# GPS_lte2.net
KiCad netlist of a schematic drawn in Altium Designer
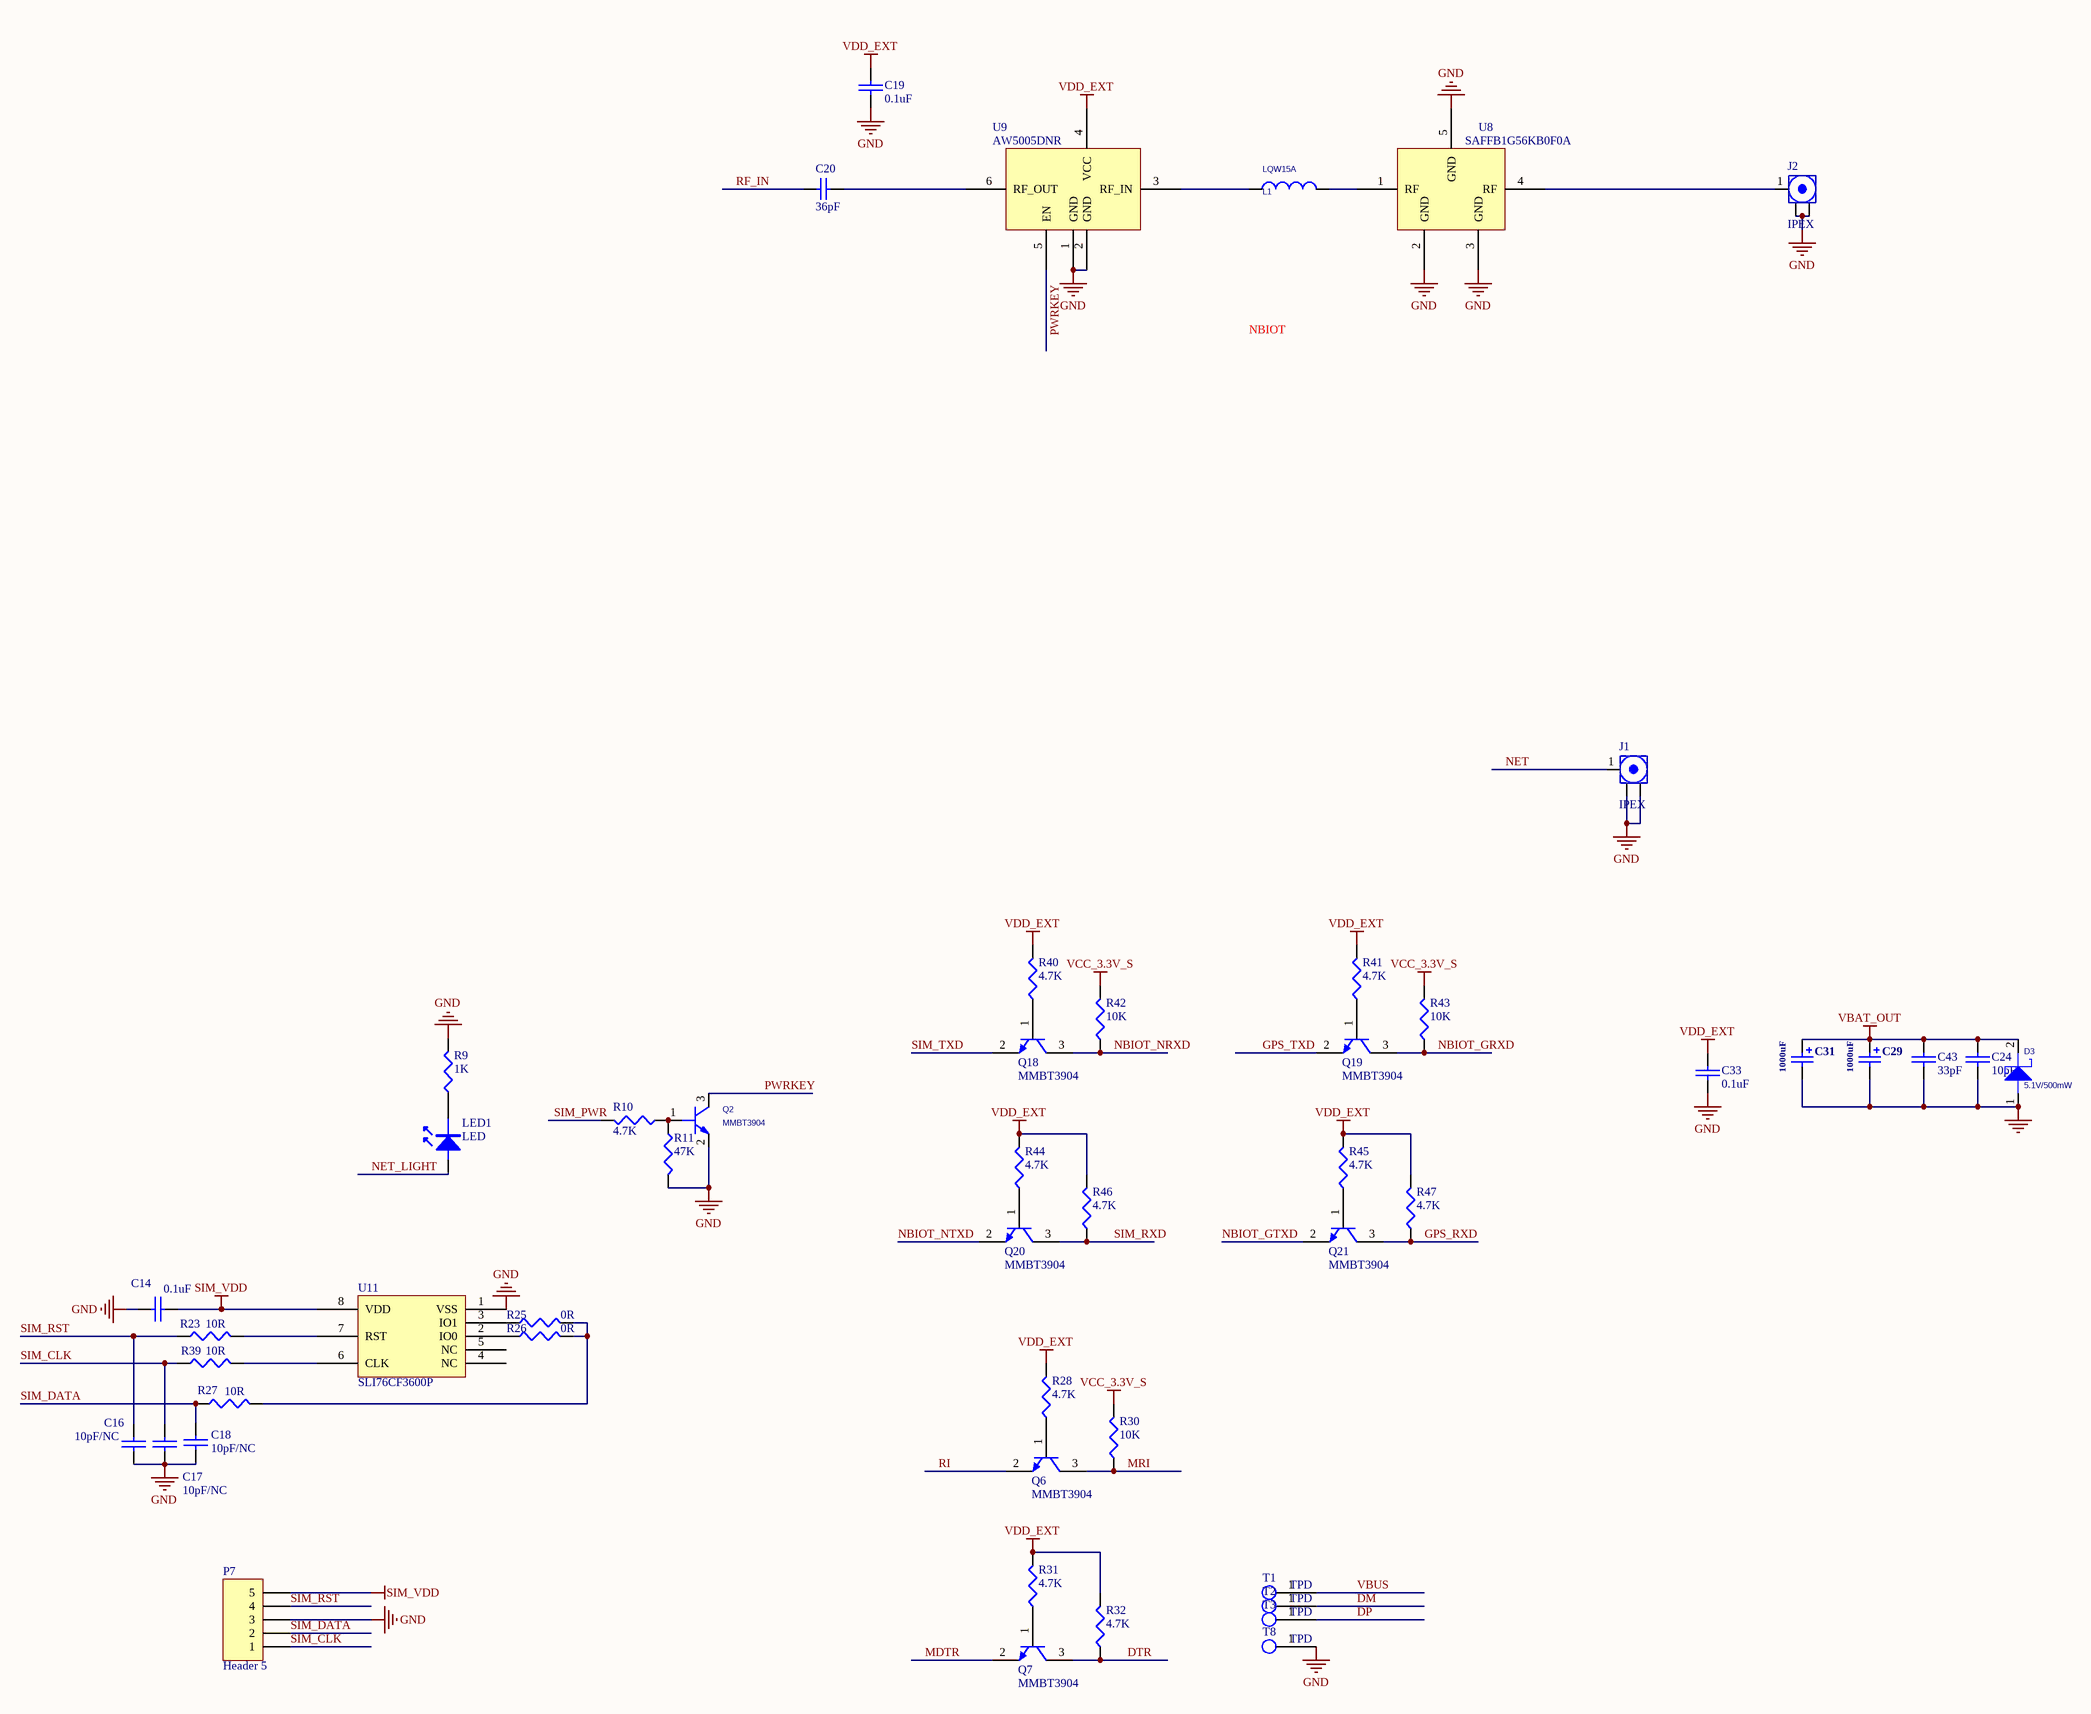
[diagram p0: GPS&&lte2.SchDoc]

(export (version "E")
  (design (tool "Eeschema 10.0.6"))
  (components
    (comp (ref "C14")
      (value "0.1uF")
      (footprint "0402C")
      (description "Capacitor")
      (libsource (lib "ZWLIntegrated_Library") (part "CAP"))
    )
    (comp (ref "C16")
      (value "10pF/NC")
      (footprint "0402C")
      (description "Capacitor")
      (libsource (lib "ZWLIntegrated_Library") (part "CAP"))
    )
    (comp (ref "C17")
      (value "10pF/NC")
      (footprint "0402C")
      (description "Capacitor")
      (libsource (lib "ZWLIntegrated_Library") (part "CAP"))
    )
    (comp (ref "C18")
      (value "10pF/NC")
      (footprint "0402C")
      (description "Capacitor")
      (libsource (lib "ZWLIntegrated_Library") (part "CAP"))
    )
    (comp (ref "C19")
      (value "0.1uF")
      (footprint "0402C")
      (description "Capacitor")
      (libsource (lib "ZWLIntegrated_Library") (part "CAP"))
    )
    (comp (ref "C20")
      (value "36pF")
      (footprint "0402c")
      (description "Capacitor")
      (fields (field (name "PUBLISHER") "Altium Limited"))
      (libsource (lib "Miscellaneous Devices") (part "Cap"))
    )
    (comp (ref "C24")
      (value "10pF")
      (footprint "0402C")
      (description "Capacitor")
      (libsource (lib "ZWLIntegrated_Library") (part "CAP"))
    )
    (comp (ref "C29")
      (value "1000uF")
      (footprint "7343")
      (description "Polarized Capacitor (Surface Mount)")
      (libsource (lib "KT_iBeacon") (part "Cap Pol3"))
    )
    (comp (ref "C31")
      (value "1000uF")
      (footprint "7343")
      (description "Polarized Capacitor (Surface Mount)")
      (libsource (lib "KT_iBeacon") (part "Cap Pol3"))
    )
    (comp (ref "C33")
      (value "0.1uF")
      (footprint "0402C")
      (description "Capacitor")
      (libsource (lib "ZWLIntegrated_Library") (part "CAP"))
    )
    (comp (ref "C43")
      (value "33pF")
      (footprint "0402C")
      (description "Capacitor")
      (libsource (lib "ZWLIntegrated_Library") (part "CAP"))
    )
    (comp (ref "D3")
      (value "5.1V/500mW")
      (footprint "LL-34(D1206)")
      (fields (field (name "Comment") "DIODE_SCHOTTKY_0"))
      (libsource (lib "KT_iBeacon") (part "DIODE_SCHOTTKY_0"))
    )
    (comp (ref "J1") (value "IPEX") (footprint "RF-UFL") (libsource (lib "我的元件库") (part "ANT")))
    (comp (ref "J2") (value "IPEX") (footprint "RF-UFL") (libsource (lib "我的元件库") (part "ANT")))
    (comp (ref "L1") (value "LQW15A") (footprint "0402R") (libsource (lib "*") (part "INDUCTOR_1")))
    (comp (ref "LED1") (value "LED") (footprint "0603LED") (libsource (lib "我的元件库") (part "LED")))
    (comp (ref "P7")
      (value "Header 5")
      (footprint "5×1.25mmSMT")
      (description "Header, 5-Pin")
      (fields (field (name "PUBLISHER") "Altium Limited"))
      (libsource (lib "Miscellaneous Connectors") (part "Header 5"))
    )
    (comp (ref "Q2") (value "MMBT3904") (footprint "SOT23-3") (libsource (lib "*") (part "2N1069_1")))
    (comp (ref "Q6") (value "MMBT3904") (footprint "SOT23-3") (libsource (lib "Schlib1") (part "NPN")))
    (comp (ref "Q7") (value "MMBT3904") (footprint "SOT23-3") (libsource (lib "Schlib1") (part "NPN")))
    (comp (ref "Q18") (value "MMBT3904") (footprint "SOT23-3") (libsource (lib "Schlib1") (part "NPN")))
    (comp (ref "Q19") (value "MMBT3904") (footprint "SOT23-3") (libsource (lib "Schlib1") (part "NPN")))
    (comp (ref "Q20") (value "MMBT3904") (footprint "SOT23-3") (libsource (lib "Schlib1") (part "NPN")))
    (comp (ref "Q21") (value "MMBT3904") (footprint "SOT23-3") (libsource (lib "Schlib1") (part "NPN")))
    (comp (ref "R9") (value "1K") (footprint "0402R") (libsource (lib "ZWLIntegrated_Library") (part "RES1")))
    (comp (ref "R10")
      (value "4.7K")
      (footprint "0402R")
      (libsource (lib "ZWLIntegrated_Library") (part "RES1"))
    )
    (comp (ref "R11")
      (value "47K")
      (footprint "0402R")
      (libsource (lib "ZWLIntegrated_Library") (part "RES1"))
    )
    (comp (ref "R23")
      (value "10R")
      (footprint "0402R")
      (libsource (lib "ZWLIntegrated_Library") (part "RES1"))
    )
    (comp (ref "R25")
      (value "0R")
      (footprint "0402R")
      (libsource (lib "ZWLIntegrated_Library") (part "RES1"))
    )
    (comp (ref "R26")
      (value "0R")
      (footprint "0402R")
      (libsource (lib "ZWLIntegrated_Library") (part "RES1"))
    )
    (comp (ref "R27")
      (value "10R")
      (footprint "0402R")
      (libsource (lib "ZWLIntegrated_Library") (part "RES1"))
    )
    (comp (ref "R28")
      (value "4.7K")
      (footprint "0402R")
      (libsource (lib "ZWLIntegrated_Library") (part "RES1"))
    )
    (comp (ref "R30")
      (value "10K")
      (footprint "0402R")
      (libsource (lib "ZWLIntegrated_Library") (part "RES1"))
    )
    (comp (ref "R31")
      (value "4.7K")
      (footprint "0402R")
      (libsource (lib "ZWLIntegrated_Library") (part "RES1"))
    )
    (comp (ref "R32")
      (value "4.7K")
      (footprint "0402R")
      (libsource (lib "ZWLIntegrated_Library") (part "RES1"))
    )
    (comp (ref "R39")
      (value "10R")
      (footprint "0402R")
      (libsource (lib "ZWLIntegrated_Library") (part "RES1"))
    )
    (comp (ref "R40")
      (value "4.7K")
      (footprint "0402R")
      (libsource (lib "ZWLIntegrated_Library") (part "RES1"))
    )
    (comp (ref "R41")
      (value "4.7K")
      (footprint "0402R")
      (libsource (lib "ZWLIntegrated_Library") (part "RES1"))
    )
    (comp (ref "R42")
      (value "10K")
      (footprint "0402R")
      (libsource (lib "ZWLIntegrated_Library") (part "RES1"))
    )
    (comp (ref "R43")
      (value "10K")
      (footprint "0402R")
      (libsource (lib "ZWLIntegrated_Library") (part "RES1"))
    )
    (comp (ref "R44")
      (value "4.7K")
      (footprint "0402R")
      (libsource (lib "ZWLIntegrated_Library") (part "RES1"))
    )
    (comp (ref "R45")
      (value "4.7K")
      (footprint "0402R")
      (libsource (lib "ZWLIntegrated_Library") (part "RES1"))
    )
    (comp (ref "R46")
      (value "4.7K")
      (footprint "0402R")
      (libsource (lib "ZWLIntegrated_Library") (part "RES1"))
    )
    (comp (ref "R47")
      (value "4.7K")
      (footprint "0402R")
      (libsource (lib "ZWLIntegrated_Library") (part "RES1"))
    )
    (comp (ref "T1") (value "TPD") (footprint "TPD") (libsource (lib "stm32") (part "TPD")))
    (comp (ref "T2") (value "TPD") (footprint "TPD") (libsource (lib "stm32") (part "TPD")))
    (comp (ref "T3") (value "TPD") (footprint "TPD") (libsource (lib "stm32") (part "TPD")))
    (comp (ref "T8") (value "TPD") (footprint "TPD") (libsource (lib "stm32") (part "TPD")))
    (comp (ref "U8")
      (value "SAFFB1G56KB0F0A")
      (footprint "SAFFB1G56KB0F0A")
      (libsource (lib "stm32") (part "SAFFB1G56KBOFA"))
    )
    (comp (ref "U9") (value "AW5005DNR") (footprint "AW5005") (libsource (lib "stm32") (part "AW5005DNR")))
    (comp (ref "U11")
      (value "SLI76CF3600P")
      (footprint "QFN127P500X600X80-8N")
      (libsource (lib "stm32") (part "SLI76CF3600P"))
    )
  )
  (nets
    (net (code "1") (name "/DM") (class "Default") (node (ref "T2") (pin "1") (pintype "passive")))
    (net (code "2") (name "/DP") (class "Default") (node (ref "T3") (pin "1") (pintype "passive")))
    (net (code "3") (name "/DTR") (class "Default")
      (node (ref "Q7") (pin "3") (pinfunction "C_3") (pintype "passive"))
      (node (ref "R32") (pin "1") (pinfunction "1_1") (pintype "passive"))
    )
    (net (code "4") (name "/GPS_RXD") (class "Default")
      (node (ref "Q21") (pin "3") (pinfunction "C_3") (pintype "passive"))
      (node (ref "R47") (pin "1") (pinfunction "1_1") (pintype "passive"))
    )
    (net (code "5") (name "/GPS_TXD") (class "Default")
      (node (ref "Q19") (pin "2") (pinfunction "E_2") (pintype "passive"))
    )
    (net (code "6") (name "/MDTR") (class "Default")
      (node (ref "Q7") (pin "2") (pinfunction "E_2") (pintype "passive"))
    )
    (net (code "7") (name "/MRI") (class "Default")
      (node (ref "Q6") (pin "3") (pinfunction "C_3") (pintype "passive"))
      (node (ref "R30") (pin "1") (pinfunction "1_1") (pintype "passive"))
    )
    (net (code "8") (name "/NBIOT_GRXD") (class "Default")
      (node (ref "Q19") (pin "3") (pinfunction "C_3") (pintype "passive"))
      (node (ref "R43") (pin "1") (pinfunction "1_1") (pintype "passive"))
    )
    (net (code "9") (name "/NBIOT_GTXD") (class "Default")
      (node (ref "Q21") (pin "2") (pinfunction "E_2") (pintype "passive"))
    )
    (net (code "10") (name "/NBIOT_NRXD") (class "Default")
      (node (ref "Q18") (pin "3") (pinfunction "C_3") (pintype "passive"))
      (node (ref "R42") (pin "1") (pinfunction "1_1") (pintype "passive"))
    )
    (net (code "11") (name "/NBIOT_NTXD") (class "Default")
      (node (ref "Q20") (pin "2") (pinfunction "E_2") (pintype "passive"))
    )
    (net (code "12") (name "/NET") (class "Default")
      (node (ref "J1") (pin "1") (pinfunction "X_1") (pintype "passive"))
    )
    (net (code "13") (name "/NET_LIGHT") (class "Default")
      (node (ref "LED1") (pin "1") (pinfunction "1_1") (pintype "passive"))
    )
    (net (code "14") (name "/PWRKEY") (class "Default")
      (node (ref "Q2") (pin "3") (pinfunction "C_3") (pintype "passive"))
      (node (ref "U9") (pin "5") (pinfunction "EN_5") (pintype "passive"))
    )
    (net (code "15") (name "/RF_IN") (class "Default")
      (node (ref "C20") (pin "1") (pinfunction "1_1") (pintype "passive"))
    )
    (net (code "16") (name "/RI") (class "Default")
      (node (ref "Q6") (pin "2") (pinfunction "E_2") (pintype "passive"))
    )
    (net (code "17") (name "/SIM_CLK") (class "Default")
      (node (ref "C17") (pin "2") (pinfunction "2_2") (pintype "passive"))
      (node (ref "P7") (pin "1") (pinfunction "1_1") (pintype "passive"))
      (node (ref "R39") (pin "1") (pinfunction "1_1") (pintype "passive"))
    )
    (net (code "18") (name "/SIM_DATA") (class "Default")
      (node (ref "C18") (pin "2") (pinfunction "2_2") (pintype "passive"))
      (node (ref "P7") (pin "2") (pinfunction "2_2") (pintype "passive"))
      (node (ref "R27") (pin "1") (pinfunction "1_1") (pintype "passive"))
    )
    (net (code "19") (name "/SIM_PWR") (class "Default")
      (node (ref "R10") (pin "2") (pinfunction "2_2") (pintype "passive"))
    )
    (net (code "20") (name "/SIM_RST") (class "Default")
      (node (ref "C16") (pin "2") (pinfunction "2_2") (pintype "passive"))
      (node (ref "P7") (pin "4") (pinfunction "4_4") (pintype "passive"))
      (node (ref "R23") (pin "1") (pinfunction "1_1") (pintype "passive"))
    )
    (net (code "21") (name "/SIM_RXD") (class "Default")
      (node (ref "Q20") (pin "3") (pinfunction "C_3") (pintype "passive"))
      (node (ref "R46") (pin "1") (pinfunction "1_1") (pintype "passive"))
    )
    (net (code "22") (name "/SIM_TXD") (class "Default")
      (node (ref "Q18") (pin "2") (pinfunction "E_2") (pintype "passive"))
    )
    (net (code "23") (name "/VBUS") (class "Default") (node (ref "T1") (pin "1") (pintype "passive")))
    (net (code "24") (name "GND") (class "Default")
      (node (ref "C14") (pin "1") (pinfunction "1_1") (pintype "passive"))
      (node (ref "C16") (pin "1") (pinfunction "1_1") (pintype "passive"))
      (node (ref "C17") (pin "1") (pinfunction "1_1") (pintype "passive"))
      (node (ref "C18") (pin "1") (pinfunction "1_1") (pintype "passive"))
      (node (ref "C19") (pin "1") (pinfunction "1_1") (pintype "passive"))
      (node (ref "C24") (pin "1") (pinfunction "1_1") (pintype "passive"))
      (node (ref "C29") (pin "2") (pinfunction "2_2") (pintype "passive"))
      (node (ref "C31") (pin "2") (pinfunction "2_2") (pintype "passive"))
      (node (ref "C33") (pin "1") (pinfunction "1_1") (pintype "passive"))
      (node (ref "C43") (pin "1") (pinfunction "1_1") (pintype "passive"))
      (node (ref "D3") (pin "1") (pinfunction "1_1") (pintype "passive"))
      (node (ref "J1") (pin "2") (pinfunction "Y_2") (pintype "passive"))
      (node (ref "J2") (pin "2") (pinfunction "Y_2") (pintype "passive"))
      (node (ref "P7") (pin "3") (pinfunction "3_3") (pintype "passive"))
      (node (ref "Q2") (pin "2") (pinfunction "E_2") (pintype "passive"))
      (node (ref "R11") (pin "2") (pinfunction "2_2") (pintype "passive"))
      (node (ref "R9") (pin "2") (pinfunction "2_2") (pintype "passive"))
      (node (ref "T8") (pin "1") (pintype "passive"))
      (node (ref "U11") (pin "1") (pinfunction "VSS_1") (pintype "passive"))
      (node (ref "U8") (pin "2") (pinfunction "GND_2") (pintype "passive"))
      (node (ref "U8") (pin "3") (pinfunction "GND_3") (pintype "passive"))
      (node (ref "U8") (pin "5") (pinfunction "GND_5") (pintype "passive"))
      (node (ref "U9") (pin "1") (pinfunction "GND_1") (pintype "passive"))
      (node (ref "U9") (pin "2") (pinfunction "GND_2") (pintype "passive"))
    )
    (net (code "25") (name "Net-(J2-X)") (class "Default")
      (node (ref "J2") (pin "1") (pinfunction "X_1") (pintype "passive"))
      (node (ref "U8") (pin "4") (pinfunction "RF_4") (pintype "passive"))
    )
    (net (code "26") (name "Net-(L1-Pad2)") (class "Default")
      (node (ref "L1") (pin "2") (pinfunction "2_2") (pintype "passive"))
      (node (ref "U8") (pin "1") (pinfunction "RF_1") (pintype "passive"))
    )
    (net (code "27") (name "Net-(LED1-Pad2)") (class "Default")
      (node (ref "LED1") (pin "2") (pinfunction "2_2") (pintype "passive"))
      (node (ref "R9") (pin "1") (pinfunction "1_1") (pintype "passive"))
    )
    (net (code "28") (name "Net-(Q2-B)") (class "Default")
      (node (ref "Q2") (pin "1") (pinfunction "B_1") (pintype "passive"))
      (node (ref "R10") (pin "1") (pinfunction "1_1") (pintype "passive"))
      (node (ref "R11") (pin "1") (pinfunction "1_1") (pintype "passive"))
    )
    (net (code "29") (name "Net-(Q6-B)") (class "Default")
      (node (ref "Q6") (pin "1") (pinfunction "B_1") (pintype "passive"))
      (node (ref "R28") (pin "1") (pinfunction "1_1") (pintype "passive"))
    )
    (net (code "30") (name "Net-(Q7-B)") (class "Default")
      (node (ref "Q7") (pin "1") (pinfunction "B_1") (pintype "passive"))
      (node (ref "R31") (pin "1") (pinfunction "1_1") (pintype "passive"))
    )
    (net (code "31") (name "Net-(Q18-B)") (class "Default")
      (node (ref "Q18") (pin "1") (pinfunction "B_1") (pintype "passive"))
      (node (ref "R40") (pin "1") (pinfunction "1_1") (pintype "passive"))
    )
    (net (code "32") (name "Net-(Q19-B)") (class "Default")
      (node (ref "Q19") (pin "1") (pinfunction "B_1") (pintype "passive"))
      (node (ref "R41") (pin "1") (pinfunction "1_1") (pintype "passive"))
    )
    (net (code "33") (name "Net-(Q20-B)") (class "Default")
      (node (ref "Q20") (pin "1") (pinfunction "B_1") (pintype "passive"))
      (node (ref "R44") (pin "1") (pinfunction "1_1") (pintype "passive"))
    )
    (net (code "34") (name "Net-(Q21-B)") (class "Default")
      (node (ref "Q21") (pin "1") (pinfunction "B_1") (pintype "passive"))
      (node (ref "R45") (pin "1") (pinfunction "1_1") (pintype "passive"))
    )
    (net (code "35") (name "Net-(R25-Pad2)") (class "Default")
      (node (ref "R25") (pin "2") (pinfunction "2_2") (pintype "passive"))
      (node (ref "R26") (pin "2") (pinfunction "2_2") (pintype "passive"))
      (node (ref "R27") (pin "2") (pinfunction "2_2") (pintype "passive"))
    )
    (net (code "36") (name "Net-(U9-RF_IN)") (class "Default")
      (node (ref "L1") (pin "1") (pinfunction "1_1") (pintype "passive"))
      (node (ref "U9") (pin "3") (pinfunction "RF_IN_3") (pintype "passive"))
    )
    (net (code "37") (name "Net-(U9-RF_OUT)") (class "Default")
      (node (ref "C20") (pin "2") (pinfunction "2_2") (pintype "passive"))
      (node (ref "U9") (pin "6") (pinfunction "RF_OUT_6") (pintype "passive"))
    )
    (net (code "38") (name "Net-(U11-CLK)") (class "Default")
      (node (ref "R39") (pin "2") (pinfunction "2_2") (pintype "passive"))
      (node (ref "U11") (pin "6") (pinfunction "CLK_6") (pintype "passive"))
    )
    (net (code "39") (name "Net-(U11-IO0)") (class "Default")
      (node (ref "R26") (pin "1") (pinfunction "1_1") (pintype "passive"))
      (node (ref "U11") (pin "2") (pinfunction "IO0_2") (pintype "passive"))
    )
    (net (code "40") (name "Net-(U11-IO1)") (class "Default")
      (node (ref "R25") (pin "1") (pinfunction "1_1") (pintype "passive"))
      (node (ref "U11") (pin "3") (pinfunction "IO1_3") (pintype "passive"))
    )
    (net (code "41") (name "Net-(U11-RST)") (class "Default")
      (node (ref "R23") (pin "2") (pinfunction "2_2") (pintype "passive"))
      (node (ref "U11") (pin "7") (pinfunction "RST_7") (pintype "passive"))
    )
    (net (code "42") (name "SIM_VDD") (class "Default")
      (node (ref "C14") (pin "2") (pinfunction "2_2") (pintype "passive"))
      (node (ref "P7") (pin "5") (pinfunction "5_5") (pintype "passive"))
      (node (ref "U11") (pin "8") (pinfunction "VDD_8") (pintype "passive"))
    )
    (net (code "43") (name "VBAT_OUT") (class "Default")
      (node (ref "C24") (pin "2") (pinfunction "2_2") (pintype "passive"))
      (node (ref "C29") (pin "1") (pinfunction "1_1") (pintype "passive"))
      (node (ref "C31") (pin "1") (pinfunction "1_1") (pintype "passive"))
      (node (ref "C43") (pin "2") (pinfunction "2_2") (pintype "passive"))
      (node (ref "D3") (pin "2") (pinfunction "2_2") (pintype "passive"))
    )
    (net (code "44") (name "VCC_3.3V_S") (class "Default")
      (node (ref "R30") (pin "2") (pinfunction "2_2") (pintype "passive"))
      (node (ref "R42") (pin "2") (pinfunction "2_2") (pintype "passive"))
      (node (ref "R43") (pin "2") (pinfunction "2_2") (pintype "passive"))
    )
    (net (code "45") (name "VDD_EXT") (class "Default")
      (node (ref "C19") (pin "2") (pinfunction "2_2") (pintype "passive"))
      (node (ref "C33") (pin "2") (pinfunction "2_2") (pintype "passive"))
      (node (ref "R28") (pin "2") (pinfunction "2_2") (pintype "passive"))
      (node (ref "R31") (pin "2") (pinfunction "2_2") (pintype "passive"))
      (node (ref "R32") (pin "2") (pinfunction "2_2") (pintype "passive"))
      (node (ref "R40") (pin "2") (pinfunction "2_2") (pintype "passive"))
      (node (ref "R41") (pin "2") (pinfunction "2_2") (pintype "passive"))
      (node (ref "R44") (pin "2") (pinfunction "2_2") (pintype "passive"))
      (node (ref "R45") (pin "2") (pinfunction "2_2") (pintype "passive"))
      (node (ref "R46") (pin "2") (pinfunction "2_2") (pintype "passive"))
      (node (ref "R47") (pin "2") (pinfunction "2_2") (pintype "passive"))
      (node (ref "U9") (pin "4") (pinfunction "VCC_4") (pintype "passive"))
    )
    (net (code "46") (name "unconnected-(U11-NC-Pad4)") (class "Default")
      (node (ref "U11") (pin "4") (pinfunction "NC_4") (pintype "passive"))
    )
    (net (code "47") (name "unconnected-(U11-NC-Pad5)") (class "Default")
      (node (ref "U11") (pin "5") (pinfunction "NC_5") (pintype "passive"))
    )
  )
)
